# Peripheral_Schematic.net
KiCad netlist of a schematic drawn in Altium Designer
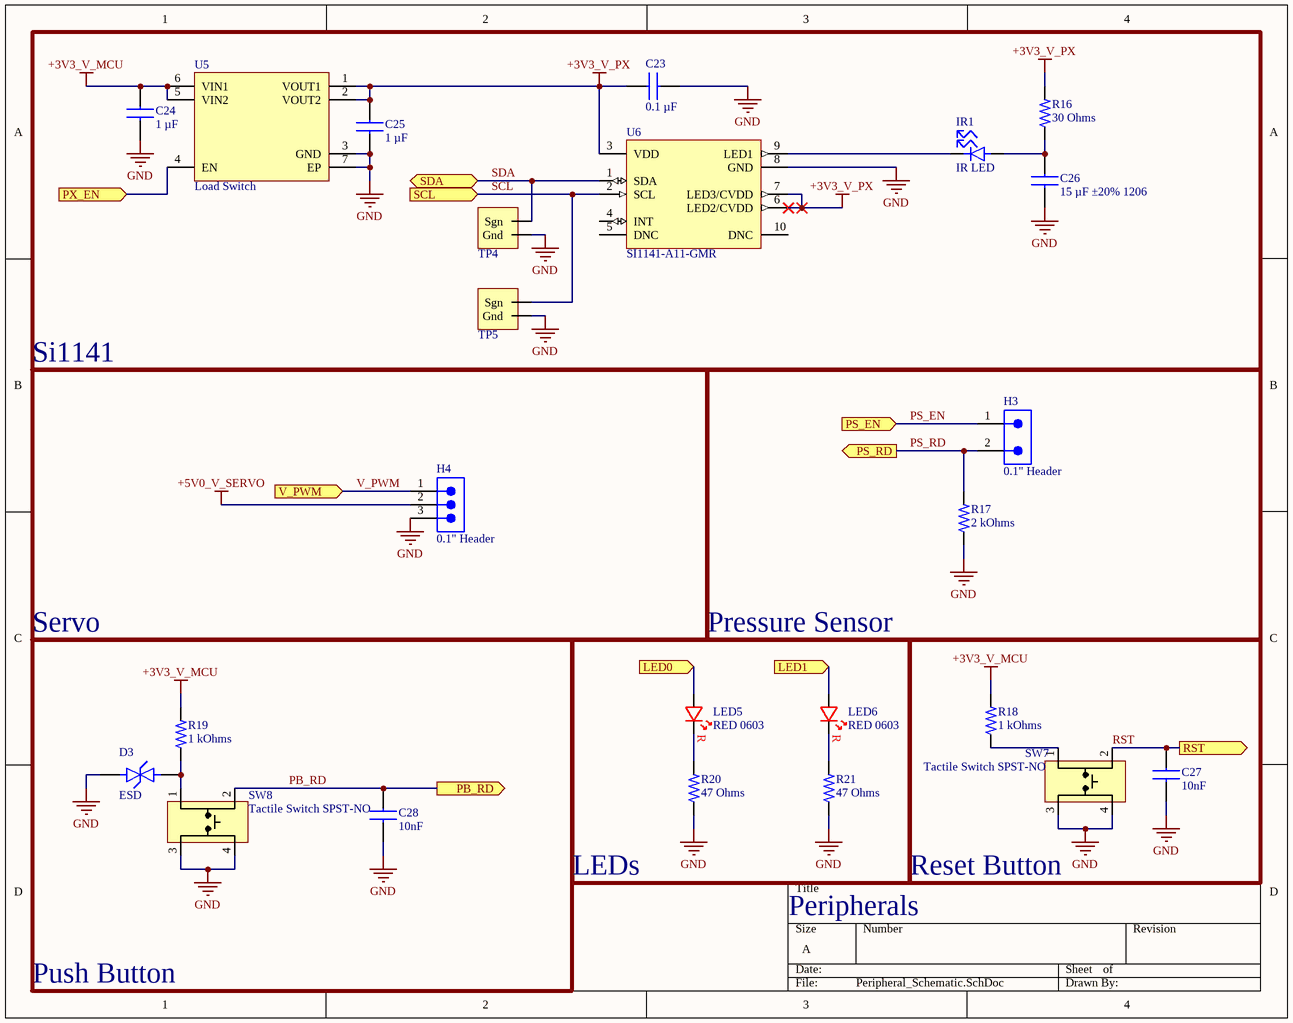
[diagram p0: Peripheral_Schematic.SchDoc]

(export (version "E")
  (design (tool "Eeschema 10.0.6"))
  (components
    (comp (ref "C23")
      (value "0.1 µF")
      (footprint "CAPC0603X09N")
      (description "Cap Cer 0603 0.1UF 16V X7R 5%")
      (fields
        (field (name "MANUFACTURER") "KEMET")
        (field (name "MANUFACTURER PART NUMBER") "C0603C104J4REC7867")
      )
      (libsource (lib "PartsLib") (part "C0603C104J4REC7867"))
    )
    (comp (ref "C24")
      (value "1 µF")
      (footprint "CAPC0603X10N")
      (description "Cap Ceramic 1uF 16V X7R 5% SMD 0603 125°C Paper T/R")
      (fields
        (field (name "MANUFACTURER") "KEMET")
        (field (name "MANUFACTURER PART NUMBER") "C0603X105J4RAC7867")
      )
      (libsource (lib "PartsLib") (part "C0603X105J4RAC7867"))
    )
    (comp (ref "C25")
      (value "1 µF")
      (footprint "CAPC0603X10N")
      (description "Cap Ceramic 1uF 16V X7R 5% SMD 0603 125°C Paper T/R")
      (fields
        (field (name "MANUFACTURER") "KEMET")
        (field (name "MANUFACTURER PART NUMBER") "C0603X105J4RAC7867")
      )
      (libsource (lib "PartsLib") (part "C0603X105J4RAC7867"))
    )
    (comp (ref "C26")
      (value "15 µF ±20% 1206")
      (footprint "CAP_1206_TDK-M")
      (description "Cap Ceramic 15uF 16V X6S 20% SMD 1206 105°C Punched Paper T/R")
      (fields
        (field (name "MANUFACTURER") "TDK")
        (field (name "MANUFACTURER PART NUMBER") "C3216X6S1C156M160AC")
      )
      (libsource (lib "PartsLib") (part "C3216X6S1C156M160AC"))
    )
    (comp (ref "C27")
      (value "10nF")
      (footprint "CAPC0603X09N")
      (description "Cap Ceramic 0.01uF 16V X7R 5% SMD 0603 125°C Paper T/R")
      (fields
        (field (name "MANUFACTURER") "KEMET")
        (field (name "MANUFACTURER PART NUMBER") "C0603C103J4RACTU")
      )
      (libsource (lib "PartsLib") (part "C0603C103J4RACTU"))
    )
    (comp (ref "C28")
      (value "10nF")
      (footprint "CAPC0603X09N")
      (description "Cap Ceramic 0.01uF 16V X7R 5% SMD 0603 125°C Paper T/R")
      (fields
        (field (name "MANUFACTURER") "KEMET")
        (field (name "MANUFACTURER PART NUMBER") "C0603C103J4RACTU")
      )
      (libsource (lib "PartsLib") (part "C0603C103J4RACTU"))
    )
    (comp (ref "D3")
      (value "ESD")
      (footprint "DFN65P100X26-2N")
      (description "15 V Bidirectional Low Capacitance ESD Protection Diode for High Speed Data Lines 15V")
      (fields
        (field (name "MANUFACTURER") "ON Semiconductor")
        (field (name "MANUFACTURER PART NUMBER") "ESDL4151MX4T5G")
      )
      (libsource (lib "PartsLib") (part "ESDL4151MX4T5G"))
    )
    (comp (ref "H3")
      (value "0.1\" Header")
      (footprint "2_PIN_100MIL")
      (description "CONN HEADER .100 DUAL STR 2POS")
      (fields (field (name "MANUFACTURER") "Sullins") (field (name "MANUFACTURER PART NUMBER") "PBC01DAAN"))
      (libsource (lib "PartsLib") (part "PBC01DAAN"))
    )
    (comp (ref "H4")
      (value "0.1\" Header")
      (footprint "3-PIN_MALE_HEADER_01-IN - duplicate")
      (description "CONN HEADER VERT 3POS 2.54MM")
      (fields
        (field (name "MANUFACTURER") "Sullins")
        (field (name "MANUFACTURER PART NUMBER") "PRPC003SAAN-RC")
      )
      (libsource (lib "PartsLib") (part "PRPC003SAAN-RC"))
    )
    (comp (ref "IR1")
      (value "IR LED")
      (footprint "LED_THROUGH-HOLE")
      (description "λP=940nm VF=1.2V View Angle=20")
      (fields (field (name "MANUFACTURER") "Everlight") (field (name "MANUFACTURER PART NUMBER") "IR333-A"))
      (libsource (lib "PartsLib") (part "IR333-A"))
    )
    (comp (ref "LED5")
      (value "RED 0603")
      (footprint "DIOC0603X06N")
      (description "0603(H=0.65mm) 红色 λD=631nm VR=5V VF=2.0V~2.4V IF=20mA PD=75mW")
      (fields
        (field (name "MANUFACTURER") "Vishay Lite-On")
        (field (name "MANUFACTURER PART NUMBER") "LTST-C191KRKT")
      )
      (libsource (lib "PartsLib") (part "LTST-C191KRKT"))
    )
    (comp (ref "LED6")
      (value "RED 0603")
      (footprint "DIOC0603X06N")
      (description "0603(H=0.65mm) 红色 λD=631nm VR=5V VF=2.0V~2.4V IF=20mA PD=75mW")
      (fields
        (field (name "MANUFACTURER") "Vishay Lite-On")
        (field (name "MANUFACTURER PART NUMBER") "LTST-C191KRKT")
      )
      (libsource (lib "PartsLib") (part "LTST-C191KRKT"))
    )
    (comp (ref "R16")
      (value "30 Ohms")
      (footprint "RESC0603X05N-2")
      (description "Res Thick Film 0603 30 Ohm 1% 1/10W ±100ppm/°C Molded SMD SMD Paper T/R")
      (fields
        (field (name "MANUFACTURER") "Stackpole Electronics")
        (field (name "MANUFACTURER PART NUMBER") "RMCF0603FT30R0")
      )
      (libsource (lib "PartsLib") (part "RMCF0603FT30R0"))
    )
    (comp (ref "R17")
      (value "2 kOhms")
      (footprint "RESC0603X05N-1")
      (description "Res Thick Film 0603 2K Ohm 1% 1/10W ±100ppm/°C Molded SMD SMD Paper T/R")
      (fields
        (field (name "MANUFACTURER") "Vishay Dale")
        (field (name "MANUFACTURER PART NUMBER") "CRCW06032K00FKTA")
      )
      (libsource (lib "PartsLib") (part "CRCW06032K00FKTA"))
    )
    (comp (ref "R18")
      (value "1 kOhms")
      (footprint "RESC0603X05N-2")
      (description "Res Thick Film 0603 1K Ohm 1% 0.1W(1/10W) ±100ppm/C Pad SMD Automotive T/R")
      (fields
        (field (name "MANUFACTURER") "Stackpole Electronics")
        (field (name "MANUFACTURER PART NUMBER") "RMCF0603FT1K00")
      )
      (libsource (lib "PartsLib") (part "RMCF0603FT1K00"))
    )
    (comp (ref "R19")
      (value "1 kOhms")
      (footprint "RESC0603X05N-2")
      (description "Res Thick Film 0603 1K Ohm 1% 0.1W(1/10W) ±100ppm/C Pad SMD Automotive T/R")
      (fields
        (field (name "MANUFACTURER") "Stackpole Electronics")
        (field (name "MANUFACTURER PART NUMBER") "RMCF0603FT1K00")
      )
      (libsource (lib "PartsLib") (part "RMCF0603FT1K00"))
    )
    (comp (ref "R20")
      (value "47 Ohms")
      (footprint "RESC0603X06N")
      (description "Res Thick Film 0603 47 Ohm 1% 1/10W ±100ppm/°C Molded SMD Paper T/R")
      (fields
        (field (name "MANUFACTURER") "Vishay Semiconductors")
        (field (name "MANUFACTURER PART NUMBER") "CRCW060347R0FKEAC")
      )
      (libsource (lib "PartsLib") (part "CRCW060347R0FKEAC"))
    )
    (comp (ref "R21")
      (value "47 Ohms")
      (footprint "RESC0603X06N")
      (description "Res Thick Film 0603 47 Ohm 1% 1/10W ±100ppm/°C Molded SMD Paper T/R")
      (fields
        (field (name "MANUFACTURER") "Vishay Semiconductors")
        (field (name "MANUFACTURER PART NUMBER") "CRCW060347R0FKEAC")
      )
      (libsource (lib "PartsLib") (part "CRCW060347R0FKEAC"))
    )
    (comp (ref "SW7")
      (value "Tactile Switch SPST-NO")
      (footprint "Switch")
      (description "TL3305A Series SPST 12 V 4.5 x 4.5 mm 160 gf Top Actuated SMT Tactile Switch")
      (fields
        (field (name "MANUFACTURER") "E-Switch")
        (field (name "MANUFACTURER PART NUMBER") "TL3305AF160QG")
      )
      (libsource (lib "PartsLib") (part "TL3305AF160QG"))
    )
    (comp (ref "SW8")
      (value "Tactile Switch SPST-NO")
      (footprint "Switch")
      (description "TL3305A Series SPST 12 V 4.5 x 4.5 mm 160 gf Top Actuated SMT Tactile Switch")
      (fields
        (field (name "MANUFACTURER") "E-Switch")
        (field (name "MANUFACTURER PART NUMBER") "TL3305AF160QG")
      )
      (libsource (lib "PartsLib") (part "TL3305AF160QG"))
    )
    (comp (ref "TP4")
      (value "10x Probe TP")
      (footprint "TP10x_Probe")
      (description "Test Point 300 mil centers")
      (libsource (lib "PartsLib") (part "TP_10x_Probe"))
    )
    (comp (ref "TP5")
      (value "10x Probe TP")
      (footprint "TP10x_Probe")
      (description "Test Point 300 mil centers")
      (libsource (lib "PartsLib") (part "TP_10x_Probe"))
    )
    (comp (ref "U5")
      (value "Load Switch")
      (footprint "SON65P200X60_HS-7N")
      (description "ICHIGH-SIDELOADSWITCH6LFCSP")
      (fields
        (field (name "MANUFACTURER") "Analog Devices")
        (field (name "MANUFACTURER PART NUMBER") "ADP196ACPZN-R7")
      )
      (libsource (lib "PartsLib") (part "ADP196ACPZN-R7"))
    )
    (comp (ref "U6")
      (value "SI1141-A11-GMR")
      (footprint "QFN10_2X2_SIL")
      (description "Proximity and Ambient Light Sensor Digital Output 1.8V/2.5V/3.3V Automotive 10-Pin QFN T/R")
      (fields (field (name "MANUFACTURER") "Silicon Labs"))
      (libsource (lib "PartsLib") (part "SI1141-A11-GMR"))
    )
  )
  (nets
    (net (code "1") (name "+3V3_V_MCU") (class "Default")
      (node (ref "C24") (pin "1") (pinfunction "1_1") (pintype "passive"))
      (node (ref "R18") (pin "2") (pinfunction "2_2") (pintype "passive"))
      (node (ref "R19") (pin "2") (pinfunction "2_2") (pintype "passive"))
      (node (ref "U5") (pin "5") (pinfunction "VIN2_5") (pintype "passive"))
      (node (ref "U5") (pin "6") (pinfunction "VIN1_6") (pintype "passive"))
    )
    (net (code "2") (name "+3V3_V_PX") (class "Default")
      (node (ref "C23") (pin "2") (pinfunction "2_2") (pintype "passive"))
      (node (ref "C25") (pin "1") (pinfunction "1_1") (pintype "passive"))
      (node (ref "R16") (pin "2") (pinfunction "2_2") (pintype "passive"))
      (node (ref "U5") (pin "1") (pinfunction "VOUT1_1") (pintype "passive"))
      (node (ref "U5") (pin "2") (pinfunction "VOUT2_2") (pintype "passive"))
      (node (ref "U6") (pin "3") (pinfunction "VDD_3") (pintype "power_in"))
      (node (ref "U6") (pin "6") (pinfunction "LED2/CVDD_6") (pintype "output"))
      (node (ref "U6") (pin "7") (pinfunction "LED3/CVDD_7") (pintype "output"))
    )
    (net (code "3") (name "+5V0_V_SERVO") (class "Default")
      (node (ref "H4") (pin "2") (pinfunction "2_2") (pintype "passive"))
    )
    (net (code "4") (name "/LED0") (class "Default")
      (node (ref "LED5") (pin "A") (pinfunction "A_A") (pintype "passive"))
    )
    (net (code "5") (name "/LED1") (class "Default")
      (node (ref "LED6") (pin "A") (pinfunction "A_A") (pintype "passive"))
    )
    (net (code "6") (name "/PB_RD") (class "Default")
      (node (ref "C28") (pin "1") (pinfunction "1_1") (pintype "passive"))
      (node (ref "SW8") (pin "2") (pinfunction "2_2") (pintype "passive"))
    )
    (net (code "7") (name "/PS_EN") (class "Default")
      (node (ref "H3") (pin "1") (pinfunction "1_1") (pintype "passive"))
    )
    (net (code "8") (name "/PS_RD") (class "Default")
      (node (ref "H3") (pin "2") (pinfunction "2_2") (pintype "passive"))
      (node (ref "R17") (pin "2") (pinfunction "2_2") (pintype "passive"))
    )
    (net (code "9") (name "/PX_EN") (class "Default")
      (node (ref "U5") (pin "4") (pinfunction "EN_4") (pintype "passive"))
    )
    (net (code "10") (name "/RST") (class "Default")
      (node (ref "C27") (pin "1") (pinfunction "1_1") (pintype "passive"))
      (node (ref "SW7") (pin "2") (pinfunction "2_2") (pintype "passive"))
    )
    (net (code "11") (name "/SCL") (class "Default")
      (node (ref "TP5") (pin "1") (pinfunction "Sgn_1") (pintype "passive"))
      (node (ref "U6") (pin "2") (pinfunction "SCL_2") (pintype "input"))
    )
    (net (code "12") (name "/SDA") (class "Default")
      (node (ref "TP4") (pin "1") (pinfunction "Sgn_1") (pintype "passive"))
      (node (ref "U6") (pin "1") (pinfunction "SDA_1") (pintype "bidirectional"))
    )
    (net (code "13") (name "/V_PWM") (class "Default")
      (node (ref "H4") (pin "1") (pinfunction "1_1") (pintype "passive"))
    )
    (net (code "14") (name "GND") (class "Default")
      (node (ref "C23") (pin "1") (pinfunction "1_1") (pintype "passive"))
      (node (ref "C24") (pin "2") (pinfunction "2_2") (pintype "passive"))
      (node (ref "C25") (pin "2") (pinfunction "2_2") (pintype "passive"))
      (node (ref "C26") (pin "2") (pinfunction "2_2") (pintype "passive"))
      (node (ref "C27") (pin "2") (pinfunction "2_2") (pintype "passive"))
      (node (ref "C28") (pin "2") (pinfunction "2_2") (pintype "passive"))
      (node (ref "D3") (pin "1") (pinfunction "1_1") (pintype "passive"))
      (node (ref "H4") (pin "3") (pinfunction "3_3") (pintype "passive"))
      (node (ref "R17") (pin "1") (pinfunction "1_1") (pintype "passive"))
      (node (ref "R20") (pin "1") (pinfunction "1_1") (pintype "passive"))
      (node (ref "R21") (pin "1") (pinfunction "1_1") (pintype "passive"))
      (node (ref "SW7") (pin "3") (pinfunction "3_3") (pintype "passive"))
      (node (ref "SW7") (pin "4") (pinfunction "4_4") (pintype "passive"))
      (node (ref "SW8") (pin "3") (pinfunction "3_3") (pintype "passive"))
      (node (ref "SW8") (pin "4") (pinfunction "4_4") (pintype "passive"))
      (node (ref "TP4") (pin "2") (pinfunction "Gnd_2") (pintype "passive"))
      (node (ref "TP5") (pin "2") (pinfunction "Gnd_2") (pintype "passive"))
      (node (ref "U5") (pin "3") (pinfunction "GND_3") (pintype "passive"))
      (node (ref "U5") (pin "7") (pinfunction "EP_7") (pintype "passive"))
      (node (ref "U6") (pin "8") (pinfunction "GND_8") (pintype "power_in"))
    )
    (net (code "15") (name "Net-(C26-Pad1)") (class "Default")
      (node (ref "C26") (pin "1") (pinfunction "1_1") (pintype "passive"))
      (node (ref "IR1") (pin "1") (pinfunction "1_1") (pintype "passive"))
      (node (ref "R16") (pin "1") (pinfunction "1_1") (pintype "passive"))
    )
    (net (code "16") (name "Net-(D3-Pad2)") (class "Default")
      (node (ref "D3") (pin "2") (pinfunction "2_2") (pintype "passive"))
      (node (ref "R19") (pin "1") (pinfunction "1_1") (pintype "passive"))
      (node (ref "SW8") (pin "1") (pinfunction "1_1") (pintype "passive"))
    )
    (net (code "17") (name "Net-(LED5-PadC)") (class "Default")
      (node (ref "LED5") (pin "C") (pinfunction "C_C") (pintype "passive"))
      (node (ref "R20") (pin "2") (pinfunction "2_2") (pintype "passive"))
    )
    (net (code "18") (name "Net-(LED6-PadC)") (class "Default")
      (node (ref "LED6") (pin "C") (pinfunction "C_C") (pintype "passive"))
      (node (ref "R21") (pin "2") (pinfunction "2_2") (pintype "passive"))
    )
    (net (code "19") (name "Net-(R18-Pad1)") (class "Default")
      (node (ref "R18") (pin "1") (pinfunction "1_1") (pintype "passive"))
      (node (ref "SW7") (pin "1") (pinfunction "1_1") (pintype "passive"))
    )
    (net (code "20") (name "Net-(U6-LED1)") (class "Default")
      (node (ref "IR1") (pin "2") (pinfunction "2_2") (pintype "passive"))
      (node (ref "U6") (pin "9") (pinfunction "LED1_9") (pintype "output"))
    )
    (net (code "21") (name "unconnected-(U6-DNC-Pad5)") (class "Default")
      (node (ref "U6") (pin "5") (pinfunction "DNC_5") (pintype "passive"))
    )
    (net (code "22") (name "unconnected-(U6-DNC-Pad10)") (class "Default")
      (node (ref "U6") (pin "10") (pinfunction "DNC_10") (pintype "passive"))
    )
    (net (code "23") (name "unconnected-(U6-INT-Pad4)") (class "Default")
      (node (ref "U6") (pin "4") (pinfunction "INT_4") (pintype "bidirectional"))
    )
  )
)
